# type-c.net
KiCad netlist of a schematic drawn in Altium Designer
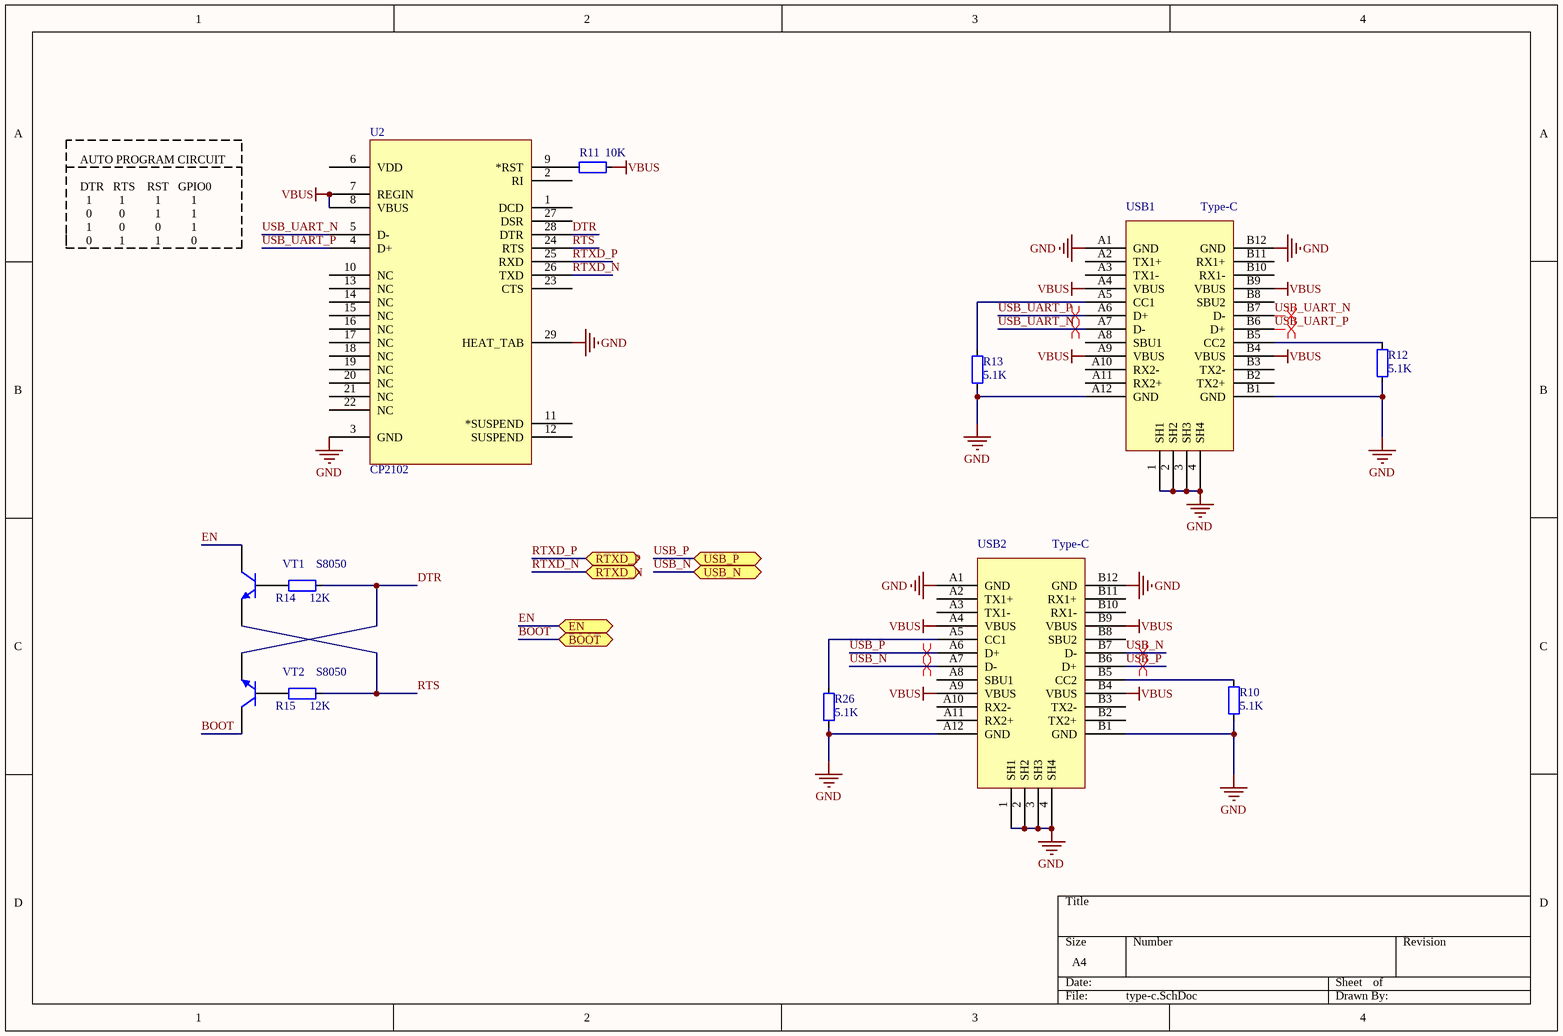
[diagram p0: type-c.SchDoc]

(export (version "E")
  (design (tool "Eeschema 10.0.6"))
  (components
    (comp (ref "R10")
      (value "5.1K")
      (footprint "RES_0402")
      (description "Resistor")
      (libsource (lib "") (part "电阻-0402_1"))
    )
    (comp (ref "R11")
      (value "10K")
      (footprint "RES_0402")
      (description "Resistor")
      (libsource (lib "MyPcbLib") (part "电阻-0402"))
    )
    (comp (ref "R12")
      (value "5.1K")
      (footprint "RES_0402")
      (description "Resistor")
      (libsource (lib "") (part "电阻-0402_1"))
    )
    (comp (ref "R13")
      (value "5.1K")
      (footprint "RES_0402")
      (description "Resistor")
      (libsource (lib "") (part "电阻-0402_1"))
    )
    (comp (ref "R14")
      (value "12K")
      (footprint "RES_0402")
      (description "Resistor")
      (libsource (lib "MyPcbLib") (part "电阻-0402"))
    )
    (comp (ref "R15")
      (value "12K")
      (footprint "RES_0402")
      (description "Resistor")
      (libsource (lib "MyPcbLib") (part "电阻-0402"))
    )
    (comp (ref "R26")
      (value "5.1K")
      (footprint "RES_0402")
      (description "Resistor")
      (libsource (lib "") (part "电阻-0402_1"))
    )
    (comp (ref "U2")
      (value "CP2102")
      (footprint "QFN-28")
      (description "USB转TTL")
      (libsource (lib "mLib") (part "CP2102"))
    )
    (comp (ref "USB1")
      (value "Type-C")
      (footprint "Type-C-TOP")
      (libsource (lib "MyPcbLib") (part "USB-Type-C-TOP"))
    )
    (comp (ref "USB2")
      (value "Type-C")
      (footprint "Type-C-TOP")
      (libsource (lib "MyPcbLib") (part "USB-Type-C-TOP"))
    )
    (comp (ref "VT1")
      (value "S8050")
      (footprint "SMT_TRIODE_NPN")
      (description "Surface mount NPN transistor, package SOT-23")
      (libsource (lib "MyPcbLib") (part "SMT_TRIODE_NPN"))
    )
    (comp (ref "VT2")
      (value "S8050")
      (footprint "SMT_TRIODE_NPN")
      (description "Surface mount NPN transistor, package SOT-23")
      (libsource (lib "MyPcbLib") (part "SMT_TRIODE_NPN"))
    )
  )
  (nets
    (net (code "1") (name "/BOOT") (class "Default")
      (node (ref "VT2") (pin "3") (pinfunction "C_3") (pintype "passive"))
    )
    (net (code "2") (name "/DTR") (class "Default")
      (node (ref "R14") (pin "1") (pinfunction "1_1") (pintype "passive"))
      (node (ref "U2") (pin "28") (pinfunction "DTR_28") (pintype "passive"))
      (node (ref "VT2") (pin "2") (pinfunction "E_2") (pintype "passive"))
    )
    (net (code "3") (name "/EN") (class "Default")
      (node (ref "VT1") (pin "3") (pinfunction "C_3") (pintype "passive"))
    )
    (net (code "4") (name "/RTS") (class "Default")
      (node (ref "R15") (pin "1") (pinfunction "1_1") (pintype "passive"))
      (node (ref "U2") (pin "24") (pinfunction "RTS_24") (pintype "passive"))
      (node (ref "VT1") (pin "2") (pinfunction "E_2") (pintype "passive"))
    )
    (net (code "5") (name "/RTXD_N") (class "Default")
      (node (ref "U2") (pin "26") (pinfunction "TXD_26") (pintype "passive"))
    )
    (net (code "6") (name "/RTXD_P") (class "Default")
      (node (ref "U2") (pin "25") (pinfunction "RXD_25") (pintype "passive"))
    )
    (net (code "7") (name "/USB_N") (class "Default")
      (node (ref "USB2") (pin "A7") (pinfunction "D-_A7") (pintype "passive"))
      (node (ref "USB2") (pin "B7") (pinfunction "D-_B7") (pintype "passive"))
    )
    (net (code "8") (name "/USB_P") (class "Default")
      (node (ref "USB2") (pin "A6") (pinfunction "D+_A6") (pintype "passive"))
      (node (ref "USB2") (pin "B6") (pinfunction "D+_B6") (pintype "passive"))
    )
    (net (code "9") (name "/USB_UART_N") (class "Default")
      (node (ref "U2") (pin "5") (pinfunction "D-_5") (pintype "passive"))
      (node (ref "USB1") (pin "A7") (pinfunction "D-_A7") (pintype "passive"))
      (node (ref "USB1") (pin "B7") (pinfunction "D-_B7") (pintype "passive"))
    )
    (net (code "10") (name "/USB_UART_P") (class "Default")
      (node (ref "U2") (pin "4") (pinfunction "D+_4") (pintype "passive"))
      (node (ref "USB1") (pin "A6") (pinfunction "D+_A6") (pintype "passive"))
      (node (ref "USB1") (pin "B6") (pinfunction "D+_B6") (pintype "passive"))
    )
    (net (code "11") (name "GND") (class "Default")
      (node (ref "R10") (pin "2") (pinfunction "2_2") (pintype "passive"))
      (node (ref "R12") (pin "2") (pinfunction "2_2") (pintype "passive"))
      (node (ref "R13") (pin "2") (pinfunction "2_2") (pintype "passive"))
      (node (ref "R26") (pin "2") (pinfunction "2_2") (pintype "passive"))
      (node (ref "U2") (pin "29") (pinfunction "HEAT_TAB_29") (pintype "passive"))
      (node (ref "U2") (pin "3") (pinfunction "GND_3") (pintype "passive"))
      (node (ref "USB1") (pin "1") (pinfunction "SH1_1") (pintype "passive"))
      (node (ref "USB1") (pin "2") (pinfunction "SH2_2") (pintype "passive"))
      (node (ref "USB1") (pin "3") (pinfunction "SH3_3") (pintype "passive"))
      (node (ref "USB1") (pin "4") (pinfunction "SH4_4") (pintype "passive"))
      (node (ref "USB1") (pin "A1") (pinfunction "GND_A1") (pintype "passive"))
      (node (ref "USB1") (pin "A12") (pinfunction "GND_A12") (pintype "passive"))
      (node (ref "USB1") (pin "B1") (pinfunction "GND_B1") (pintype "passive"))
      (node (ref "USB1") (pin "B12") (pinfunction "GND_B12") (pintype "passive"))
      (node (ref "USB2") (pin "1") (pinfunction "SH1_1") (pintype "passive"))
      (node (ref "USB2") (pin "2") (pinfunction "SH2_2") (pintype "passive"))
      (node (ref "USB2") (pin "3") (pinfunction "SH3_3") (pintype "passive"))
      (node (ref "USB2") (pin "4") (pinfunction "SH4_4") (pintype "passive"))
      (node (ref "USB2") (pin "A1") (pinfunction "GND_A1") (pintype "passive"))
      (node (ref "USB2") (pin "A12") (pinfunction "GND_A12") (pintype "passive"))
      (node (ref "USB2") (pin "B1") (pinfunction "GND_B1") (pintype "passive"))
      (node (ref "USB2") (pin "B12") (pinfunction "GND_B12") (pintype "passive"))
    )
    (net (code "12") (name "Net-(U2-*RST)") (class "Default")
      (node (ref "R11") (pin "2") (pinfunction "2_2") (pintype "passive"))
      (node (ref "U2") (pin "9") (pinfunction "*RST_9") (pintype "passive"))
    )
    (net (code "13") (name "Net-(USB1-CC1)") (class "Default")
      (node (ref "R13") (pin "1") (pinfunction "1_1") (pintype "passive"))
      (node (ref "USB1") (pin "A5") (pinfunction "CC1_A5") (pintype "passive"))
    )
    (net (code "14") (name "Net-(USB1-CC2)") (class "Default")
      (node (ref "R12") (pin "1") (pinfunction "1_1") (pintype "passive"))
      (node (ref "USB1") (pin "B5") (pinfunction "CC2_B5") (pintype "passive"))
    )
    (net (code "15") (name "Net-(USB2-CC1)") (class "Default")
      (node (ref "R26") (pin "1") (pinfunction "1_1") (pintype "passive"))
      (node (ref "USB2") (pin "A5") (pinfunction "CC1_A5") (pintype "passive"))
    )
    (net (code "16") (name "Net-(USB2-CC2)") (class "Default")
      (node (ref "R10") (pin "1") (pinfunction "1_1") (pintype "passive"))
      (node (ref "USB2") (pin "B5") (pinfunction "CC2_B5") (pintype "passive"))
    )
    (net (code "17") (name "Net-(VT1-B)") (class "Default")
      (node (ref "R14") (pin "2") (pinfunction "2_2") (pintype "passive"))
      (node (ref "VT1") (pin "1") (pinfunction "B_1") (pintype "passive"))
    )
    (net (code "18") (name "Net-(VT2-B)") (class "Default")
      (node (ref "R15") (pin "2") (pinfunction "2_2") (pintype "passive"))
      (node (ref "VT2") (pin "1") (pinfunction "B_1") (pintype "passive"))
    )
    (net (code "19") (name "VBUS") (class "Default")
      (node (ref "R11") (pin "1") (pinfunction "1_1") (pintype "passive"))
      (node (ref "U2") (pin "7") (pinfunction "REGIN_7") (pintype "passive"))
      (node (ref "U2") (pin "8") (pinfunction "VBUS_8") (pintype "passive"))
      (node (ref "USB1") (pin "A4") (pinfunction "VBUS_A4") (pintype "passive"))
      (node (ref "USB1") (pin "A9") (pinfunction "VBUS_A9") (pintype "passive"))
      (node (ref "USB1") (pin "B4") (pinfunction "VBUS_B4") (pintype "passive"))
      (node (ref "USB1") (pin "B9") (pinfunction "VBUS_B9") (pintype "passive"))
      (node (ref "USB2") (pin "A4") (pinfunction "VBUS_A4") (pintype "passive"))
      (node (ref "USB2") (pin "A9") (pinfunction "VBUS_A9") (pintype "passive"))
      (node (ref "USB2") (pin "B4") (pinfunction "VBUS_B4") (pintype "passive"))
      (node (ref "USB2") (pin "B9") (pinfunction "VBUS_B9") (pintype "passive"))
    )
    (net (code "20") (name "unconnected-(U2-*SUSPEND-Pad11)") (class "Default")
      (node (ref "U2") (pin "11") (pinfunction "*SUSPEND_11") (pintype "passive"))
    )
    (net (code "21") (name "unconnected-(U2-CTS-Pad23)") (class "Default")
      (node (ref "U2") (pin "23") (pinfunction "CTS_23") (pintype "passive"))
    )
    (net (code "22") (name "unconnected-(U2-DCD-Pad1)") (class "Default")
      (node (ref "U2") (pin "1") (pinfunction "DCD_1") (pintype "passive"))
    )
    (net (code "23") (name "unconnected-(U2-DSR-Pad27)") (class "Default")
      (node (ref "U2") (pin "27") (pinfunction "DSR_27") (pintype "passive"))
    )
    (net (code "24") (name "unconnected-(U2-NC-Pad10)") (class "Default")
      (node (ref "U2") (pin "10") (pinfunction "NC_10") (pintype "passive"))
    )
    (net (code "25") (name "unconnected-(U2-NC-Pad13)") (class "Default")
      (node (ref "U2") (pin "13") (pinfunction "NC_13") (pintype "passive"))
    )
    (net (code "26") (name "unconnected-(U2-NC-Pad14)") (class "Default")
      (node (ref "U2") (pin "14") (pinfunction "NC_14") (pintype "passive"))
    )
    (net (code "27") (name "unconnected-(U2-NC-Pad15)") (class "Default")
      (node (ref "U2") (pin "15") (pinfunction "NC_15") (pintype "passive"))
    )
    (net (code "28") (name "unconnected-(U2-NC-Pad16)") (class "Default")
      (node (ref "U2") (pin "16") (pinfunction "NC_16") (pintype "passive"))
    )
    (net (code "29") (name "unconnected-(U2-NC-Pad17)") (class "Default")
      (node (ref "U2") (pin "17") (pinfunction "NC_17") (pintype "passive"))
    )
    (net (code "30") (name "unconnected-(U2-NC-Pad18)") (class "Default")
      (node (ref "U2") (pin "18") (pinfunction "NC_18") (pintype "passive"))
    )
    (net (code "31") (name "unconnected-(U2-NC-Pad19)") (class "Default")
      (node (ref "U2") (pin "19") (pinfunction "NC_19") (pintype "passive"))
    )
    (net (code "32") (name "unconnected-(U2-NC-Pad20)") (class "Default")
      (node (ref "U2") (pin "20") (pinfunction "NC_20") (pintype "passive"))
    )
    (net (code "33") (name "unconnected-(U2-NC-Pad21)") (class "Default")
      (node (ref "U2") (pin "21") (pinfunction "NC_21") (pintype "passive"))
    )
    (net (code "34") (name "unconnected-(U2-NC-Pad22)") (class "Default")
      (node (ref "U2") (pin "22") (pinfunction "NC_22") (pintype "passive"))
    )
    (net (code "35") (name "unconnected-(U2-RI-Pad2)") (class "Default")
      (node (ref "U2") (pin "2") (pinfunction "RI_2") (pintype "passive"))
    )
    (net (code "36") (name "unconnected-(U2-SUSPEND-Pad12)") (class "Default")
      (node (ref "U2") (pin "12") (pinfunction "SUSPEND_12") (pintype "passive"))
    )
    (net (code "37") (name "unconnected-(U2-VDD-Pad6)") (class "Default")
      (node (ref "U2") (pin "6") (pinfunction "VDD_6") (pintype "passive"))
    )
    (net (code "38") (name "unconnected-(USB1-RX1+-PadB11)") (class "Default")
      (node (ref "USB1") (pin "B11") (pinfunction "RX1+_B11") (pintype "passive"))
    )
    (net (code "39") (name "unconnected-(USB1-RX1--PadB10)") (class "Default")
      (node (ref "USB1") (pin "B10") (pinfunction "RX1-_B10") (pintype "passive"))
    )
    (net (code "40") (name "unconnected-(USB1-RX2+-PadA11)") (class "Default")
      (node (ref "USB1") (pin "A11") (pinfunction "RX2+_A11") (pintype "passive"))
    )
    (net (code "41") (name "unconnected-(USB1-RX2--PadA10)") (class "Default")
      (node (ref "USB1") (pin "A10") (pinfunction "RX2-_A10") (pintype "passive"))
    )
    (net (code "42") (name "unconnected-(USB1-SBU1-PadA8)") (class "Default")
      (node (ref "USB1") (pin "A8") (pinfunction "SBU1_A8") (pintype "passive"))
    )
    (net (code "43") (name "unconnected-(USB1-SBU2-PadB8)") (class "Default")
      (node (ref "USB1") (pin "B8") (pinfunction "SBU2_B8") (pintype "passive"))
    )
    (net (code "44") (name "unconnected-(USB1-TX1+-PadA2)") (class "Default")
      (node (ref "USB1") (pin "A2") (pinfunction "TX1+_A2") (pintype "passive"))
    )
    (net (code "45") (name "unconnected-(USB1-TX1--PadA3)") (class "Default")
      (node (ref "USB1") (pin "A3") (pinfunction "TX1-_A3") (pintype "passive"))
    )
    (net (code "46") (name "unconnected-(USB1-TX2+-PadB2)") (class "Default")
      (node (ref "USB1") (pin "B2") (pinfunction "TX2+_B2") (pintype "passive"))
    )
    (net (code "47") (name "unconnected-(USB1-TX2--PadB3)") (class "Default")
      (node (ref "USB1") (pin "B3") (pinfunction "TX2-_B3") (pintype "passive"))
    )
    (net (code "48") (name "unconnected-(USB2-RX1+-PadB11)") (class "Default")
      (node (ref "USB2") (pin "B11") (pinfunction "RX1+_B11") (pintype "passive"))
    )
    (net (code "49") (name "unconnected-(USB2-RX1--PadB10)") (class "Default")
      (node (ref "USB2") (pin "B10") (pinfunction "RX1-_B10") (pintype "passive"))
    )
    (net (code "50") (name "unconnected-(USB2-RX2+-PadA11)") (class "Default")
      (node (ref "USB2") (pin "A11") (pinfunction "RX2+_A11") (pintype "passive"))
    )
    (net (code "51") (name "unconnected-(USB2-RX2--PadA10)") (class "Default")
      (node (ref "USB2") (pin "A10") (pinfunction "RX2-_A10") (pintype "passive"))
    )
    (net (code "52") (name "unconnected-(USB2-SBU1-PadA8)") (class "Default")
      (node (ref "USB2") (pin "A8") (pinfunction "SBU1_A8") (pintype "passive"))
    )
    (net (code "53") (name "unconnected-(USB2-SBU2-PadB8)") (class "Default")
      (node (ref "USB2") (pin "B8") (pinfunction "SBU2_B8") (pintype "passive"))
    )
    (net (code "54") (name "unconnected-(USB2-TX1+-PadA2)") (class "Default")
      (node (ref "USB2") (pin "A2") (pinfunction "TX1+_A2") (pintype "passive"))
    )
    (net (code "55") (name "unconnected-(USB2-TX1--PadA3)") (class "Default")
      (node (ref "USB2") (pin "A3") (pinfunction "TX1-_A3") (pintype "passive"))
    )
    (net (code "56") (name "unconnected-(USB2-TX2+-PadB2)") (class "Default")
      (node (ref "USB2") (pin "B2") (pinfunction "TX2+_B2") (pintype "passive"))
    )
    (net (code "57") (name "unconnected-(USB2-TX2--PadB3)") (class "Default")
      (node (ref "USB2") (pin "B3") (pinfunction "TX2-_B3") (pintype "passive"))
    )
  )
)
